# virajgandhi_servo_attiny44_with5v_regula.net
KiCad netlist of a schematic drawn in EAGLE
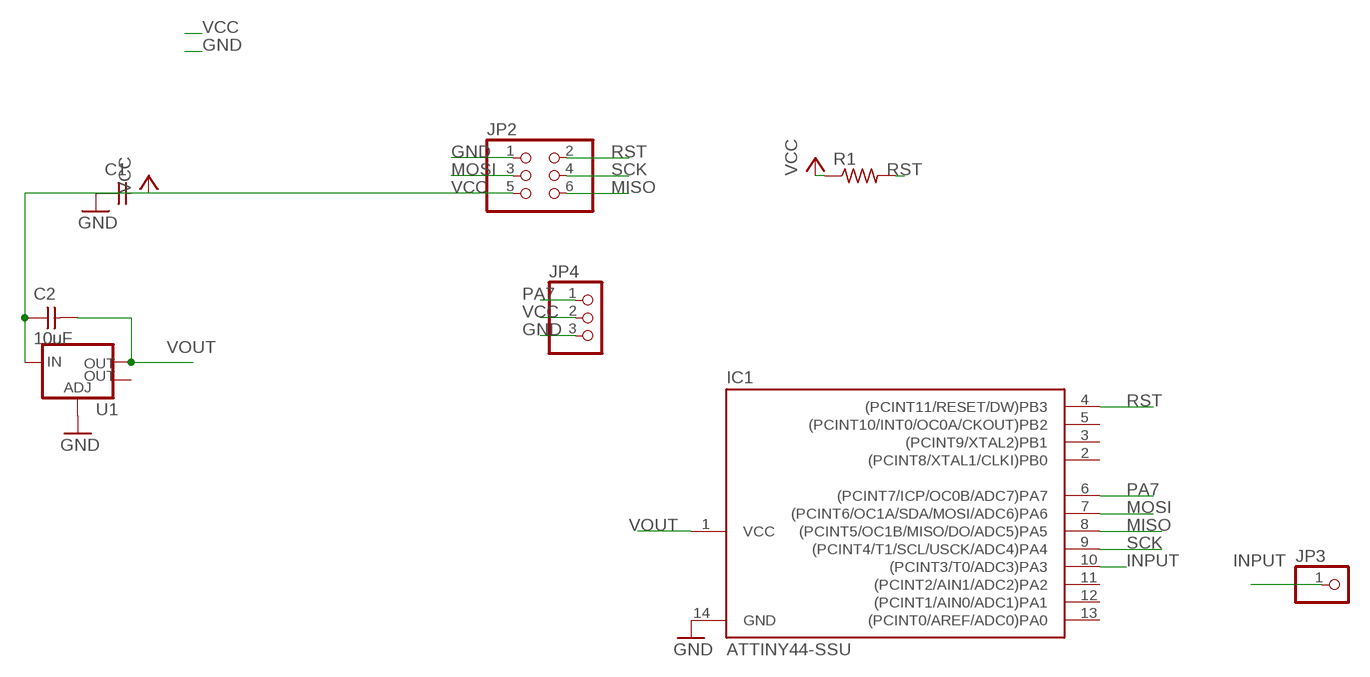
[diagram p0: schematic, sheet 1]

(export (version "E")
  (design (tool "Eeschema 10.0.6"))
  (components
    (comp (ref "C1")
      (value "CAP-UNPOLARIZEDFAB")
      (footprint "eagle-import:C1206FAB")
      (libsource (lib "eagle-import") (part "CAP-UNPOLARIZEDFAB"))
    )
    (comp (ref "C2")
      (value "10uF")
      (footprint "eagle-import:C1206FAB")
      (libsource (lib "eagle-import") (part "CAP-UNPOLARIZEDFAB"))
    )
    (comp (ref "IC1")
      (value "ATTINY44-SSU")
      (footprint "eagle-import:SOIC14")
      (libsource (lib "eagle-import") (part "ATTINY44-SSU"))
    )
    (comp (ref "JP2")
      (value "PINHD-2X3-SMD")
      (footprint "eagle-import:2X03SMD")
      (libsource (lib "eagle-import") (part "PINHD-2X3-SMD"))
    )
    (comp (ref "JP3")
      (value "PINHD-1X1")
      (footprint "eagle-import:1X01")
      (libsource (lib "eagle-import") (part "PINHD-1X1"))
    )
    (comp (ref "JP4")
      (value "PINHD-1X3")
      (footprint "eagle-import:1X03")
      (libsource (lib "eagle-import") (part "PINHD-1X3"))
    )
    (comp (ref "R1")
      (value "RES-US1206FAB")
      (footprint "eagle-import:R1206FAB")
      (libsource (lib "eagle-import") (part "RES-US1206FAB"))
    )
    (comp (ref "U1")
      (value "V_REG_LM1117SOT223")
      (footprint "eagle-import:SOT223")
      (libsource (lib "eagle-import") (part "V_REG_LM1117SOT223"))
    )
  )
  (nets
    (net (code "1") (name "/INPUT") (class "Default")
      (node (ref "IC1") (pin "10") (pinfunction "(PCINT3/T0/ADC3)PA3_10") (pintype "bidirectional"))
      (node (ref "JP3") (pin "1") (pinfunction "1_1") (pintype "passive"))
    )
    (net (code "2") (name "/MISO") (class "Default")
      (node (ref "IC1") (pin "8") (pinfunction "(PCINT5/OC1B/MISO/DO/ADC5)PA5_8") (pintype "bidirectional"))
      (node (ref "JP2") (pin "6") (pinfunction "6_6") (pintype "passive"))
    )
    (net (code "3") (name "/MOSI") (class "Default")
      (node (ref "IC1") (pin "7") (pinfunction "(PCINT6/OC1A/SDA/MOSI/ADC6)PA6_7") (pintype "bidirectional"))
      (node (ref "JP2") (pin "3") (pinfunction "3_3") (pintype "passive"))
    )
    (net (code "4") (name "/PA7") (class "Default")
      (node (ref "IC1") (pin "6") (pinfunction "(PCINT7/ICP/OC0B/ADC7)PA7_6") (pintype "bidirectional"))
      (node (ref "JP4") (pin "1") (pinfunction "1_1") (pintype "passive"))
    )
    (net (code "5") (name "/RST") (class "Default")
      (node (ref "IC1") (pin "4") (pinfunction "(PCINT11/RESET/DW)PB3_4") (pintype "bidirectional"))
      (node (ref "JP2") (pin "2") (pinfunction "2_2") (pintype "passive"))
      (node (ref "R1") (pin "2") (pinfunction "2_2") (pintype "passive"))
    )
    (net (code "6") (name "/SCK") (class "Default")
      (node (ref "IC1") (pin "9") (pinfunction "(PCINT4/T1/SCL/USCK/ADC4)PA4_9") (pintype "bidirectional"))
      (node (ref "JP2") (pin "4") (pinfunction "4_4") (pintype "passive"))
    )
    (net (code "7") (name "/VOUT") (class "Default")
      (node (ref "C2") (pin "2") (pinfunction "2_2") (pintype "passive"))
      (node (ref "IC1") (pin "1") (pinfunction "VCC_1") (pintype "power_in"))
      (node (ref "U1") (pin "2") (pinfunction "OUT_2") (pintype "output"))
    )
    (net (code "8") (name "GND") (class "Default")
      (node (ref "C1") (pin "1") (pinfunction "1_1") (pintype "passive"))
      (node (ref "IC1") (pin "14") (pinfunction "GND_14") (pintype "power_in"))
      (node (ref "JP2") (pin "1") (pinfunction "1_1") (pintype "passive"))
      (node (ref "JP4") (pin "3") (pinfunction "3_3") (pintype "passive"))
      (node (ref "U1") (pin "1") (pinfunction "ADJ_1") (pintype "input"))
    )
    (net (code "9") (name "VCC") (class "Default")
      (node (ref "C1") (pin "2") (pinfunction "2_2") (pintype "passive"))
      (node (ref "C2") (pin "1") (pinfunction "1_1") (pintype "passive"))
      (node (ref "JP2") (pin "5") (pinfunction "5_5") (pintype "passive"))
      (node (ref "JP4") (pin "2") (pinfunction "2_2") (pintype "passive"))
      (node (ref "R1") (pin "1") (pinfunction "1_1") (pintype "passive"))
      (node (ref "U1") (pin "3") (pinfunction "IN_3") (pintype "input"))
    )
    (net (code "10") (name "unconnected-(IC1-(PCINT0{slash}AREF{slash}ADC0)PA0-Pad13)") (class "Default")
      (node (ref "IC1") (pin "13") (pinfunction "(PCINT0/AREF/ADC0)PA0_13") (pintype "bidirectional"))
    )
    (net (code "11") (name "unconnected-(IC1-(PCINT1{slash}AIN0{slash}ADC1)PA1-Pad12)") (class "Default")
      (node (ref "IC1") (pin "12") (pinfunction "(PCINT1/AIN0/ADC1)PA1_12") (pintype "bidirectional"))
    )
    (net (code "12") (name "unconnected-(IC1-(PCINT2{slash}AIN1{slash}ADC2)PA2-Pad11)") (class "Default")
      (node (ref "IC1") (pin "11") (pinfunction "(PCINT2/AIN1/ADC2)PA2_11") (pintype "bidirectional"))
    )
    (net (code "13") (name "unconnected-(IC1-(PCINT8{slash}XTAL1{slash}CLKI)PB0-Pad2)") (class "Default")
      (node (ref "IC1") (pin "2") (pinfunction "(PCINT8/XTAL1/CLKI)PB0_2") (pintype "bidirectional"))
    )
    (net (code "14") (name "unconnected-(IC1-(PCINT9{slash}XTAL2)PB1-Pad3)") (class "Default")
      (node (ref "IC1") (pin "3") (pinfunction "(PCINT9/XTAL2)PB1_3") (pintype "bidirectional"))
    )
    (net (code "15") (name "unconnected-(IC1-(PCINT10{slash}INT0{slash}OC0A{slash}CKOUT)PB2-Pad5)") (class "Default")
      (node (ref "IC1") (pin "5") (pinfunction "(PCINT10/INT0/OC0A/CKOUT)PB2_5") (pintype "bidirectional"))
    )
    (net (code "16") (name "unconnected-(U1-OUT-Pad4)") (class "Default")
      (node (ref "U1") (pin "4") (pinfunction "OUT_4") (pintype "output"))
    )
  )
)
